# Neopixel.net
KiCad netlist of a schematic drawn in Altium Designer
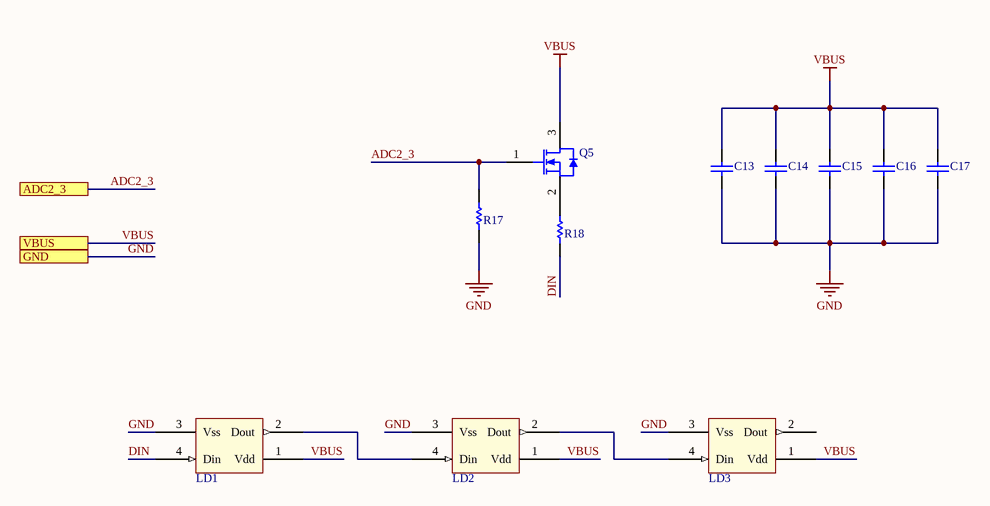
[diagram p0: Neopixel.SchDoc]

(export (version "E")
  (design (tool "Eeschema 10.0.6"))
  (components
    (comp (ref "C13")
      (value "C0805C105K4RAC7800")
      (footprint "CAPC2013X145X50NL20T25")
      (description "1µF ±10% 16V Ceramic Capacitor X7R 0805 (2012 Metric)")
      (fields (field (name "MANUFACTURER") "Kemet"))
      (libsource (lib "Altium Content Vault") (part "CAP"))
    )
    (comp (ref "C14")
      (value "C0805C105K4RAC7800")
      (footprint "CAPC2013X145X50NL20T25")
      (description "1µF ±10% 16V Ceramic Capacitor X7R 0805 (2012 Metric)")
      (fields (field (name "MANUFACTURER") "Kemet"))
      (libsource (lib "Altium Content Vault") (part "CAP"))
    )
    (comp (ref "C15")
      (value "C0805C105K4RAC7800")
      (footprint "CAPC2013X145X50NL20T25")
      (description "1µF ±10% 16V Ceramic Capacitor X7R 0805 (2012 Metric)")
      (fields (field (name "MANUFACTURER") "Kemet"))
      (libsource (lib "Altium Content Vault") (part "CAP"))
    )
    (comp (ref "C16")
      (value "C0805C105K4RAC7800")
      (footprint "CAPC2013X145X50NL20T25")
      (description "1µF ±10% 16V Ceramic Capacitor X7R 0805 (2012 Metric)")
      (fields (field (name "MANUFACTURER") "Kemet"))
      (libsource (lib "Altium Content Vault") (part "CAP"))
    )
    (comp (ref "C17")
      (value "C0805C105K4RAC7800")
      (footprint "CAPC2013X145X50NL20T25")
      (description "1µF ±10% 16V Ceramic Capacitor X7R 0805 (2012 Metric)")
      (fields (field (name "MANUFACTURER") "Kemet"))
      (libsource (lib "Altium Content Vault") (part "CAP"))
    )
    (comp (ref "LD1")
      (value "WS2812B-B")
      (footprint "WS2812B")
      (description "Neopixel Led 5050- ws2812b RGB")
      (libsource (lib "LIB_FIT") (part "WS2812B"))
    )
    (comp (ref "LD2")
      (value "WS2812B-B")
      (footprint "WS2812B")
      (description "Neopixel Led 5050- ws2812b RGB")
      (libsource (lib "LIB_FIT") (part "WS2812B"))
    )
    (comp (ref "LD3")
      (value "WS2812B-B")
      (footprint "WS2812B")
      (description "Neopixel Led 5050- ws2812b RGB")
      (libsource (lib "LIB_FIT") (part "WS2812B"))
    )
    (comp (ref "Q5")
      (value "BSS138-7-F")
      (footprint "DIOD-SOT23-3_V")
      (description "N-Channel Enhancement Mode Mosfet, 50 V, 0.2 A, -55 to 150 degC, 3-Pin SOT23, RoHS, Tape and Reel")
      (fields (field (name "MANUFACTURER") "Diodes Inc"))
      (libsource (lib "Altium Content Vault") (part "NEMOS-GSD-3"))
    )
    (comp (ref "R17")
      (value "RK73B2ATTD103J")
      (footprint "RESC2013X60X30NL20T20")
      (fields (field (name "MANUFACTURER") "KOA Speer"))
      (libsource (lib "Altium Content Vault") (part "RES"))
    )
    (comp (ref "R18")
      (value "RK73B2ATTD471J")
      (footprint "RESC2013X60X30NL20T20")
      (fields (field (name "MANUFACTURER") "KOA Speer"))
      (libsource (lib "Altium Content Vault") (part "RES"))
    )
  )
  (nets
    (net (code "1") (name "/ADC2_3") (class "Default")
      (node (ref "Q5") (pin "1") (pinfunction "G_1") (pintype "passive"))
      (node (ref "R17") (pin "1") (pinfunction "1_1") (pintype "passive"))
    )
    (net (code "2") (name "/DIN") (class "Default")
      (node (ref "LD1") (pin "4") (pinfunction "Din_4") (pintype "input"))
      (node (ref "R18") (pin "1") (pinfunction "1_1") (pintype "passive"))
    )
    (net (code "3") (name "GND") (class "Default")
      (node (ref "C13") (pin "1") (pinfunction "1_1") (pintype "passive"))
      (node (ref "C14") (pin "1") (pinfunction "1_1") (pintype "passive"))
      (node (ref "C15") (pin "1") (pinfunction "1_1") (pintype "passive"))
      (node (ref "C16") (pin "1") (pinfunction "1_1") (pintype "passive"))
      (node (ref "C17") (pin "1") (pinfunction "1_1") (pintype "passive"))
      (node (ref "LD1") (pin "3") (pinfunction "Vss_3") (pintype "power_in"))
      (node (ref "LD2") (pin "3") (pinfunction "Vss_3") (pintype "power_in"))
      (node (ref "LD3") (pin "3") (pinfunction "Vss_3") (pintype "power_in"))
      (node (ref "R17") (pin "2") (pinfunction "2_2") (pintype "passive"))
    )
    (net (code "4") (name "Net-(LD1-Dout)") (class "Default")
      (node (ref "LD1") (pin "2") (pinfunction "Dout_2") (pintype "output"))
      (node (ref "LD2") (pin "4") (pinfunction "Din_4") (pintype "input"))
    )
    (net (code "5") (name "Net-(LD2-Dout)") (class "Default")
      (node (ref "LD2") (pin "2") (pinfunction "Dout_2") (pintype "output"))
      (node (ref "LD3") (pin "4") (pinfunction "Din_4") (pintype "input"))
    )
    (net (code "6") (name "Net-(Q5-S)") (class "Default")
      (node (ref "Q5") (pin "2") (pinfunction "S_2") (pintype "passive"))
      (node (ref "R18") (pin "2") (pinfunction "2_2") (pintype "passive"))
    )
    (net (code "7") (name "VBUS") (class "Default")
      (node (ref "C13") (pin "2") (pinfunction "2_2") (pintype "passive"))
      (node (ref "C14") (pin "2") (pinfunction "2_2") (pintype "passive"))
      (node (ref "C15") (pin "2") (pinfunction "2_2") (pintype "passive"))
      (node (ref "C16") (pin "2") (pinfunction "2_2") (pintype "passive"))
      (node (ref "C17") (pin "2") (pinfunction "2_2") (pintype "passive"))
      (node (ref "LD1") (pin "1") (pinfunction "Vdd_1") (pintype "power_in"))
      (node (ref "LD2") (pin "1") (pinfunction "Vdd_1") (pintype "power_in"))
      (node (ref "LD3") (pin "1") (pinfunction "Vdd_1") (pintype "power_in"))
      (node (ref "Q5") (pin "3") (pinfunction "D_3") (pintype "passive"))
    )
    (net (code "8") (name "unconnected-(LD3-Dout-Pad2)") (class "Default")
      (node (ref "LD3") (pin "2") (pinfunction "Dout_2") (pintype "output"))
    )
  )
)
